# LineCliffSensors.net
KiCad netlist of a schematic drawn in Altium Designer
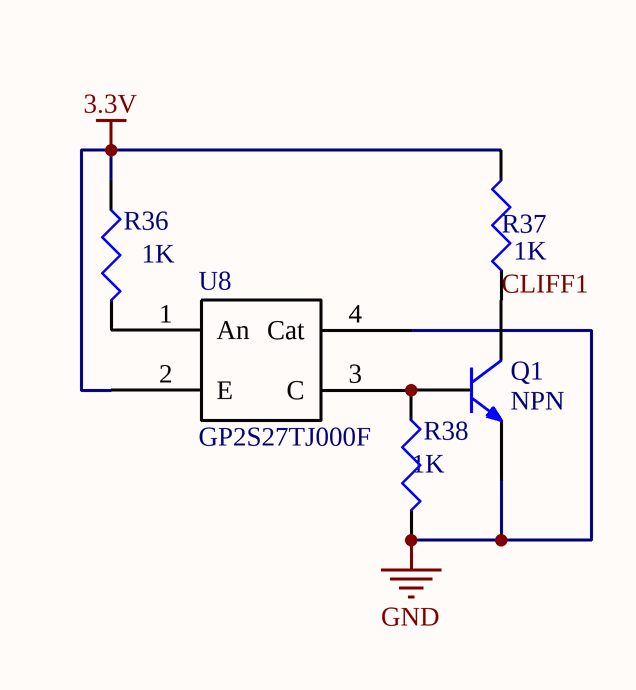
[diagram p0: LineCliffSensors.SchDoc]

(export (version "E")
  (design (tool "Eeschema 10.0.6"))
  (components
    (comp (ref "Q1") (value "NPN") (footprint "SOT-23") (libsource (lib "mrone") (part "NPN")))
    (comp (ref "R36")
      (value "1K")
      (footprint "RESC1608L")
      (description "Resistor")
      (fields (field (name "Comment") "Res3") (field (name "PUBLISHER") "Altium Limited"))
      (libsource (lib "Miscellaneous Devices") (part "Res3"))
    )
    (comp (ref "R37")
      (value "1K")
      (footprint "RESC1608L")
      (description "Resistor")
      (fields (field (name "Comment") "Res3") (field (name "PUBLISHER") "Altium Limited"))
      (libsource (lib "Miscellaneous Devices") (part "Res3"))
    )
    (comp (ref "R38")
      (value "1K")
      (footprint "RESC1608L")
      (description "Resistor")
      (fields (field (name "Comment") "Res3") (field (name "PUBLISHER") "Altium Limited"))
      (libsource (lib "Miscellaneous Devices") (part "Res3"))
    )
    (comp (ref "U8")
      (value "GP2S27TJ000F")
      (footprint "GP2S27J0000F")
      (libsource (lib "mrone") (part "GP2S27TJ000F"))
    )
  )
  (nets
    (net (code "1") (name "/CLIFF1") (class "Default")
      (node (ref "Q1") (pin "3") (pinfunction "C_3") (pintype "passive"))
      (node (ref "R37") (pin "1") (pinfunction "1_1") (pintype "passive"))
    )
    (net (code "2") (name "3.3V") (class "Default")
      (node (ref "R36") (pin "1") (pinfunction "1_1") (pintype "passive"))
      (node (ref "R37") (pin "2") (pinfunction "2_2") (pintype "passive"))
      (node (ref "U8") (pin "2") (pinfunction "E_2") (pintype "passive"))
    )
    (net (code "3") (name "GND") (class "Default")
      (node (ref "Q1") (pin "2") (pinfunction "E_2") (pintype "passive"))
      (node (ref "R38") (pin "2") (pinfunction "2_2") (pintype "passive"))
      (node (ref "U8") (pin "4") (pinfunction "Cat_4") (pintype "passive"))
    )
    (net (code "4") (name "Net-(Q1-B)") (class "Default")
      (node (ref "Q1") (pin "1") (pinfunction "B_1") (pintype "passive"))
      (node (ref "R38") (pin "1") (pinfunction "1_1") (pintype "passive"))
      (node (ref "U8") (pin "3") (pinfunction "C_3") (pintype "passive"))
    )
    (net (code "5") (name "Net-(U8-An)") (class "Default")
      (node (ref "R36") (pin "2") (pinfunction "2_2") (pintype "passive"))
      (node (ref "U8") (pin "1") (pinfunction "An_1") (pintype "passive"))
    )
  )
)
